# Flash.net
KiCad netlist of a schematic drawn in Altium Designer
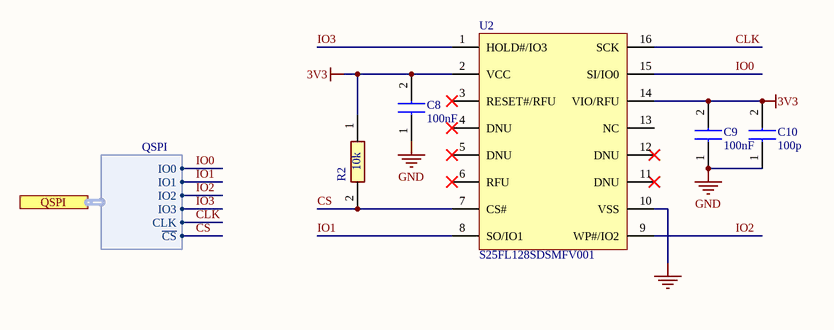
[diagram p0: Flash.SchDoc]

(export (version "E")
  (design (tool "Eeschema 10.0.6"))
  (components
    (comp (ref "C8")
      (value "100nF")
      (footprint "SamacSys:CAPC1005X70N")
      (description "Capacitor")
      (fields
        (field (name "MANUFACTURER_PART_NUMBER") "GRM155R61A104KA01D")
        (field (name "MOUSER PART NUMBER") "81-GRM155R61A104KA01")
      )
      (libsource (lib "*") (part "GRM155R61A104KA01D"))
    )
    (comp (ref "C9")
      (value "100nF")
      (footprint "SamacSys:CAPC1005X70N")
      (description "Capacitor")
      (fields
        (field (name "MANUFACTURER_PART_NUMBER") "GRM155R61A104KA01D")
        (field (name "MOUSER PART NUMBER") "81-GRM155R61A104KA01")
      )
      (libsource (lib "*") (part "GRM155R61A104KA01D"))
    )
    (comp (ref "C10")
      (value "100p")
      (footprint "SamacSys:CAPC1005X70N")
      (description "Capacitor")
      (fields
        (field (name "MANUFACTURER_PART_NUMBER") "GRM1555C1E101JA01D")
        (field (name "MOUSER PART NUMBER") "81-GRM1555C1E101JA1D")
      )
      (libsource (lib "*") (part "GRM1555C1E101JA01D"))
    )
    (comp (ref "R2")
      (value "10k")
      (footprint "SamacSys:RESC1005X35N")
      (description "Resistor")
      (fields
        (field (name "MANUFACTURER_PART_NUMBER") "RT0402FRE0710KL")
        (field (name "MOUSER PART NUMBER") "603-RT0402FRE0710KL")
      )
      (libsource (lib "SamacSys") (part "RT0402FRE0710KL"))
    )
    (comp (ref "U2")
      (value "S25FL128SDSMFV001")
      (footprint "ICC_SOIC16_10P30X7P50_P127_H2P65")
      (description "Quad SPI with SOIC package 16-pins")
      (fields (field (name "INTERNAL_PART_NUMBER") "MCD-02038") (field (name "MANUFACTURER") "CYPRESS"))
      (libsource (lib "SamacSys") (part "S25FL128SDSMFV001"))
    )
  )
  (nets
    (net (code "2") (name "/CLK") (class "Default")
      (node (ref "U2") (pin "16") (pinfunction "SCK_16") (pintype "passive"))
    )
    (net (code "3") (name "/CS") (class "Default")
      (node (ref "R2") (pin "2") (pinfunction "2_2") (pintype "passive"))
      (node (ref "U2") (pin "7") (pinfunction "CS#_7") (pintype "passive"))
    )
    (net (code "4") (name "/IO0") (class "Default")
      (node (ref "U2") (pin "15") (pinfunction "SI/IO0_15") (pintype "passive"))
    )
    (net (code "5") (name "/IO1") (class "Default")
      (node (ref "U2") (pin "8") (pinfunction "SO/IO1_8") (pintype "passive"))
    )
    (net (code "6") (name "/IO2") (class "Default")
      (node (ref "U2") (pin "9") (pinfunction "WP#/IO2_9") (pintype "passive"))
    )
    (net (code "7") (name "/IO3") (class "Default")
      (node (ref "U2") (pin "1") (pinfunction "HOLD#/IO3_1") (pintype "passive"))
    )
    (net (code "9") (name "3V3") (class "Default")
      (node (ref "C10") (pin "2") (pinfunction "2_2") (pintype "passive"))
      (node (ref "C8") (pin "2") (pinfunction "2_2") (pintype "passive"))
      (node (ref "C9") (pin "2") (pinfunction "2_2") (pintype "passive"))
      (node (ref "R2") (pin "1") (pinfunction "1_1") (pintype "passive"))
      (node (ref "U2") (pin "14") (pinfunction "VIO/RFU_14") (pintype "passive"))
      (node (ref "U2") (pin "2") (pinfunction "VCC_2") (pintype "passive"))
    )
    (net (code "10") (name "GND") (class "Default")
      (node (ref "C10") (pin "1") (pinfunction "1_1") (pintype "passive"))
      (node (ref "C8") (pin "1") (pinfunction "1_1") (pintype "passive"))
      (node (ref "C9") (pin "1") (pinfunction "1_1") (pintype "passive"))
      (node (ref "U2") (pin "10") (pinfunction "VSS_10") (pintype "passive"))
    )
    (net (code "11") (name "unconnected-(U2-DNU-Pad4)") (class "Default")
      (node (ref "U2") (pin "4") (pinfunction "DNU_4") (pintype "passive+no_connect"))
    )
    (net (code "12") (name "unconnected-(U2-DNU-Pad5)") (class "Default")
      (node (ref "U2") (pin "5") (pinfunction "DNU_5") (pintype "passive+no_connect"))
    )
    (net (code "13") (name "unconnected-(U2-DNU-Pad11)") (class "Default")
      (node (ref "U2") (pin "11") (pinfunction "DNU_11") (pintype "passive+no_connect"))
    )
    (net (code "14") (name "unconnected-(U2-DNU-Pad12)") (class "Default")
      (node (ref "U2") (pin "12") (pinfunction "DNU_12") (pintype "passive+no_connect"))
    )
    (net (code "15") (name "unconnected-(U2-NC-Pad13)") (class "Default")
      (node (ref "U2") (pin "13") (pinfunction "NC_13") (pintype "passive"))
    )
    (net (code "16") (name "unconnected-(U2-RESET#{slash}RFU-Pad3)") (class "Default")
      (node (ref "U2") (pin "3") (pinfunction "RESET#/RFU_3") (pintype "passive+no_connect"))
    )
    (net (code "17") (name "unconnected-(U2-RFU-Pad6)") (class "Default")
      (node (ref "U2") (pin "6") (pinfunction "RFU_6") (pintype "passive+no_connect"))
    )
  )
)
